# bmsMaster_led.net
KiCad netlist of a schematic drawn in Altium Designer
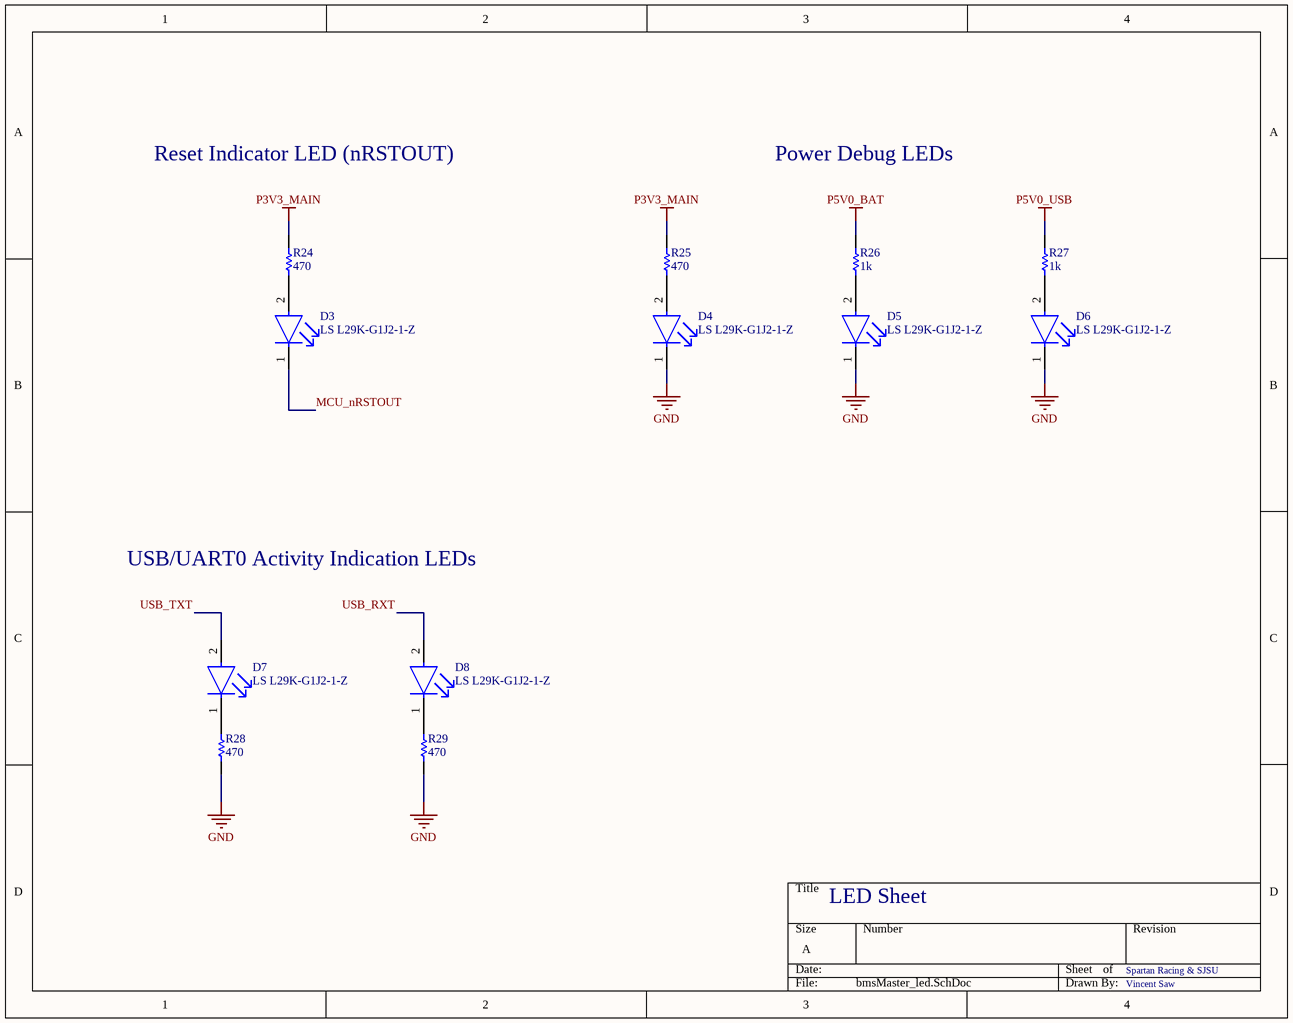
[diagram p0: bmsMaster_led.SchDoc]

(export (version "E")
  (design (tool "Eeschema 10.0.6"))
  (components
    (comp (ref "D3")
      (value "LS L29K-G1J2-1-Z")
      (footprint "FP-LS_L29K-MFG")
      (description "LED RED DIFFUSED 0603 SMD")
      (fields
        (field (name "MANUFACTURER") "Osram Opto")
        (field (name "OCTOPART") "https://octopart.com/ls+l29k-g1j2-1-z-osram+opto-31093939")
      )
      (libsource (lib "Altium Content Vault") (part "8706943c75ba83719d021d2fdc84c58"))
    )
    (comp (ref "D4")
      (value "LS L29K-G1J2-1-Z")
      (footprint "FP-LS_L29K-MFG")
      (description "LED RED DIFFUSED 0603 SMD")
      (fields
        (field (name "MANUFACTURER") "Osram Opto")
        (field (name "OCTOPART") "https://octopart.com/ls+l29k-g1j2-1-z-osram+opto-31093939")
      )
      (libsource (lib "Altium Content Vault") (part "8706943c75ba83719d021d2fdc84c58"))
    )
    (comp (ref "D5")
      (value "LS L29K-G1J2-1-Z")
      (footprint "FP-LS_L29K-MFG")
      (description "LED RED DIFFUSED 0603 SMD")
      (fields
        (field (name "MANUFACTURER") "Osram Opto")
        (field (name "OCTOPART") "https://octopart.com/ls+l29k-g1j2-1-z-osram+opto-31093939")
      )
      (libsource (lib "Altium Content Vault") (part "8706943c75ba83719d021d2fdc84c58"))
    )
    (comp (ref "D6")
      (value "LS L29K-G1J2-1-Z")
      (footprint "FP-LS_L29K-MFG")
      (description "LED RED DIFFUSED 0603 SMD")
      (fields
        (field (name "MANUFACTURER") "Osram Opto")
        (field (name "OCTOPART") "https://octopart.com/ls+l29k-g1j2-1-z-osram+opto-31093939")
      )
      (libsource (lib "Altium Content Vault") (part "8706943c75ba83719d021d2fdc84c58"))
    )
    (comp (ref "D7")
      (value "LS L29K-G1J2-1-Z")
      (footprint "FP-LS_L29K-MFG")
      (description "LED RED DIFFUSED 0603 SMD")
      (fields
        (field (name "MANUFACTURER") "Osram Opto")
        (field (name "OCTOPART") "https://octopart.com/ls+l29k-g1j2-1-z-osram+opto-31093939")
      )
      (libsource (lib "Altium Content Vault") (part "8706943c75ba83719d021d2fdc84c58"))
    )
    (comp (ref "D8")
      (value "LS L29K-G1J2-1-Z")
      (footprint "FP-LS_L29K-MFG")
      (description "LED RED DIFFUSED 0603 SMD")
      (fields
        (field (name "MANUFACTURER") "Osram Opto")
        (field (name "OCTOPART") "https://octopart.com/ls+l29k-g1j2-1-z-osram+opto-31093939")
      )
      (libsource (lib "Altium Content Vault") (part "8706943c75ba83719d021d2fdc84c58"))
    )
    (comp (ref "R24")
      (value "470")
      (description "Resistor")
      (libsource (lib "Simulation Generic Components") (part "Resistor"))
    )
    (comp (ref "R25")
      (value "470")
      (description "Resistor")
      (libsource (lib "Simulation Generic Components") (part "Resistor"))
    )
    (comp (ref "R26")
      (value "1k")
      (description "Resistor")
      (libsource (lib "Simulation Generic Components") (part "Resistor"))
    )
    (comp (ref "R27")
      (value "1k")
      (description "Resistor")
      (libsource (lib "Simulation Generic Components") (part "Resistor"))
    )
    (comp (ref "R28")
      (value "470")
      (description "Resistor")
      (libsource (lib "Simulation Generic Components") (part "Resistor"))
    )
    (comp (ref "R29")
      (value "470")
      (description "Resistor")
      (libsource (lib "Simulation Generic Components") (part "Resistor"))
    )
  )
  (nets
    (net (code "1") (name "/MCU_nRSTOUT") (class "Default")
      (node (ref "D3") (pin "1") (pinfunction "C_1") (pintype "passive"))
    )
    (net (code "2") (name "/USB_RXT") (class "Default")
      (node (ref "D8") (pin "2") (pinfunction "A_2") (pintype "passive"))
    )
    (net (code "3") (name "/USB_TXT") (class "Default")
      (node (ref "D7") (pin "2") (pinfunction "A_2") (pintype "passive"))
    )
    (net (code "4") (name "GND") (class "Default")
      (node (ref "D4") (pin "1") (pinfunction "C_1") (pintype "passive"))
      (node (ref "D5") (pin "1") (pinfunction "C_1") (pintype "passive"))
      (node (ref "D6") (pin "1") (pinfunction "C_1") (pintype "passive"))
      (node (ref "R28") (pin "1") (pinfunction "1_1") (pintype "passive"))
      (node (ref "R29") (pin "1") (pinfunction "1_1") (pintype "passive"))
    )
    (net (code "5") (name "Net-(D3-A)") (class "Default")
      (node (ref "D3") (pin "2") (pinfunction "A_2") (pintype "passive"))
      (node (ref "R24") (pin "1") (pinfunction "1_1") (pintype "passive"))
    )
    (net (code "6") (name "Net-(D4-A)") (class "Default")
      (node (ref "D4") (pin "2") (pinfunction "A_2") (pintype "passive"))
      (node (ref "R25") (pin "1") (pinfunction "1_1") (pintype "passive"))
    )
    (net (code "7") (name "Net-(D5-A)") (class "Default")
      (node (ref "D5") (pin "2") (pinfunction "A_2") (pintype "passive"))
      (node (ref "R26") (pin "1") (pinfunction "1_1") (pintype "passive"))
    )
    (net (code "8") (name "Net-(D6-A)") (class "Default")
      (node (ref "D6") (pin "2") (pinfunction "A_2") (pintype "passive"))
      (node (ref "R27") (pin "1") (pinfunction "1_1") (pintype "passive"))
    )
    (net (code "9") (name "Net-(D7-C)") (class "Default")
      (node (ref "D7") (pin "1") (pinfunction "C_1") (pintype "passive"))
      (node (ref "R28") (pin "2") (pinfunction "2_2") (pintype "passive"))
    )
    (net (code "10") (name "Net-(D8-C)") (class "Default")
      (node (ref "D8") (pin "1") (pinfunction "C_1") (pintype "passive"))
      (node (ref "R29") (pin "2") (pinfunction "2_2") (pintype "passive"))
    )
    (net (code "11") (name "P3V3_MAIN") (class "Default")
      (node (ref "R24") (pin "2") (pinfunction "2_2") (pintype "passive"))
      (node (ref "R25") (pin "2") (pinfunction "2_2") (pintype "passive"))
    )
    (net (code "12") (name "P5V0_BAT") (class "Default")
      (node (ref "R26") (pin "2") (pinfunction "2_2") (pintype "passive"))
    )
    (net (code "13") (name "P5V0_USB") (class "Default")
      (node (ref "R27") (pin "2") (pinfunction "2_2") (pintype "passive"))
    )
  )
)
